# Leonardo_Rev3d.net
KiCad netlist of a schematic drawn in EAGLE
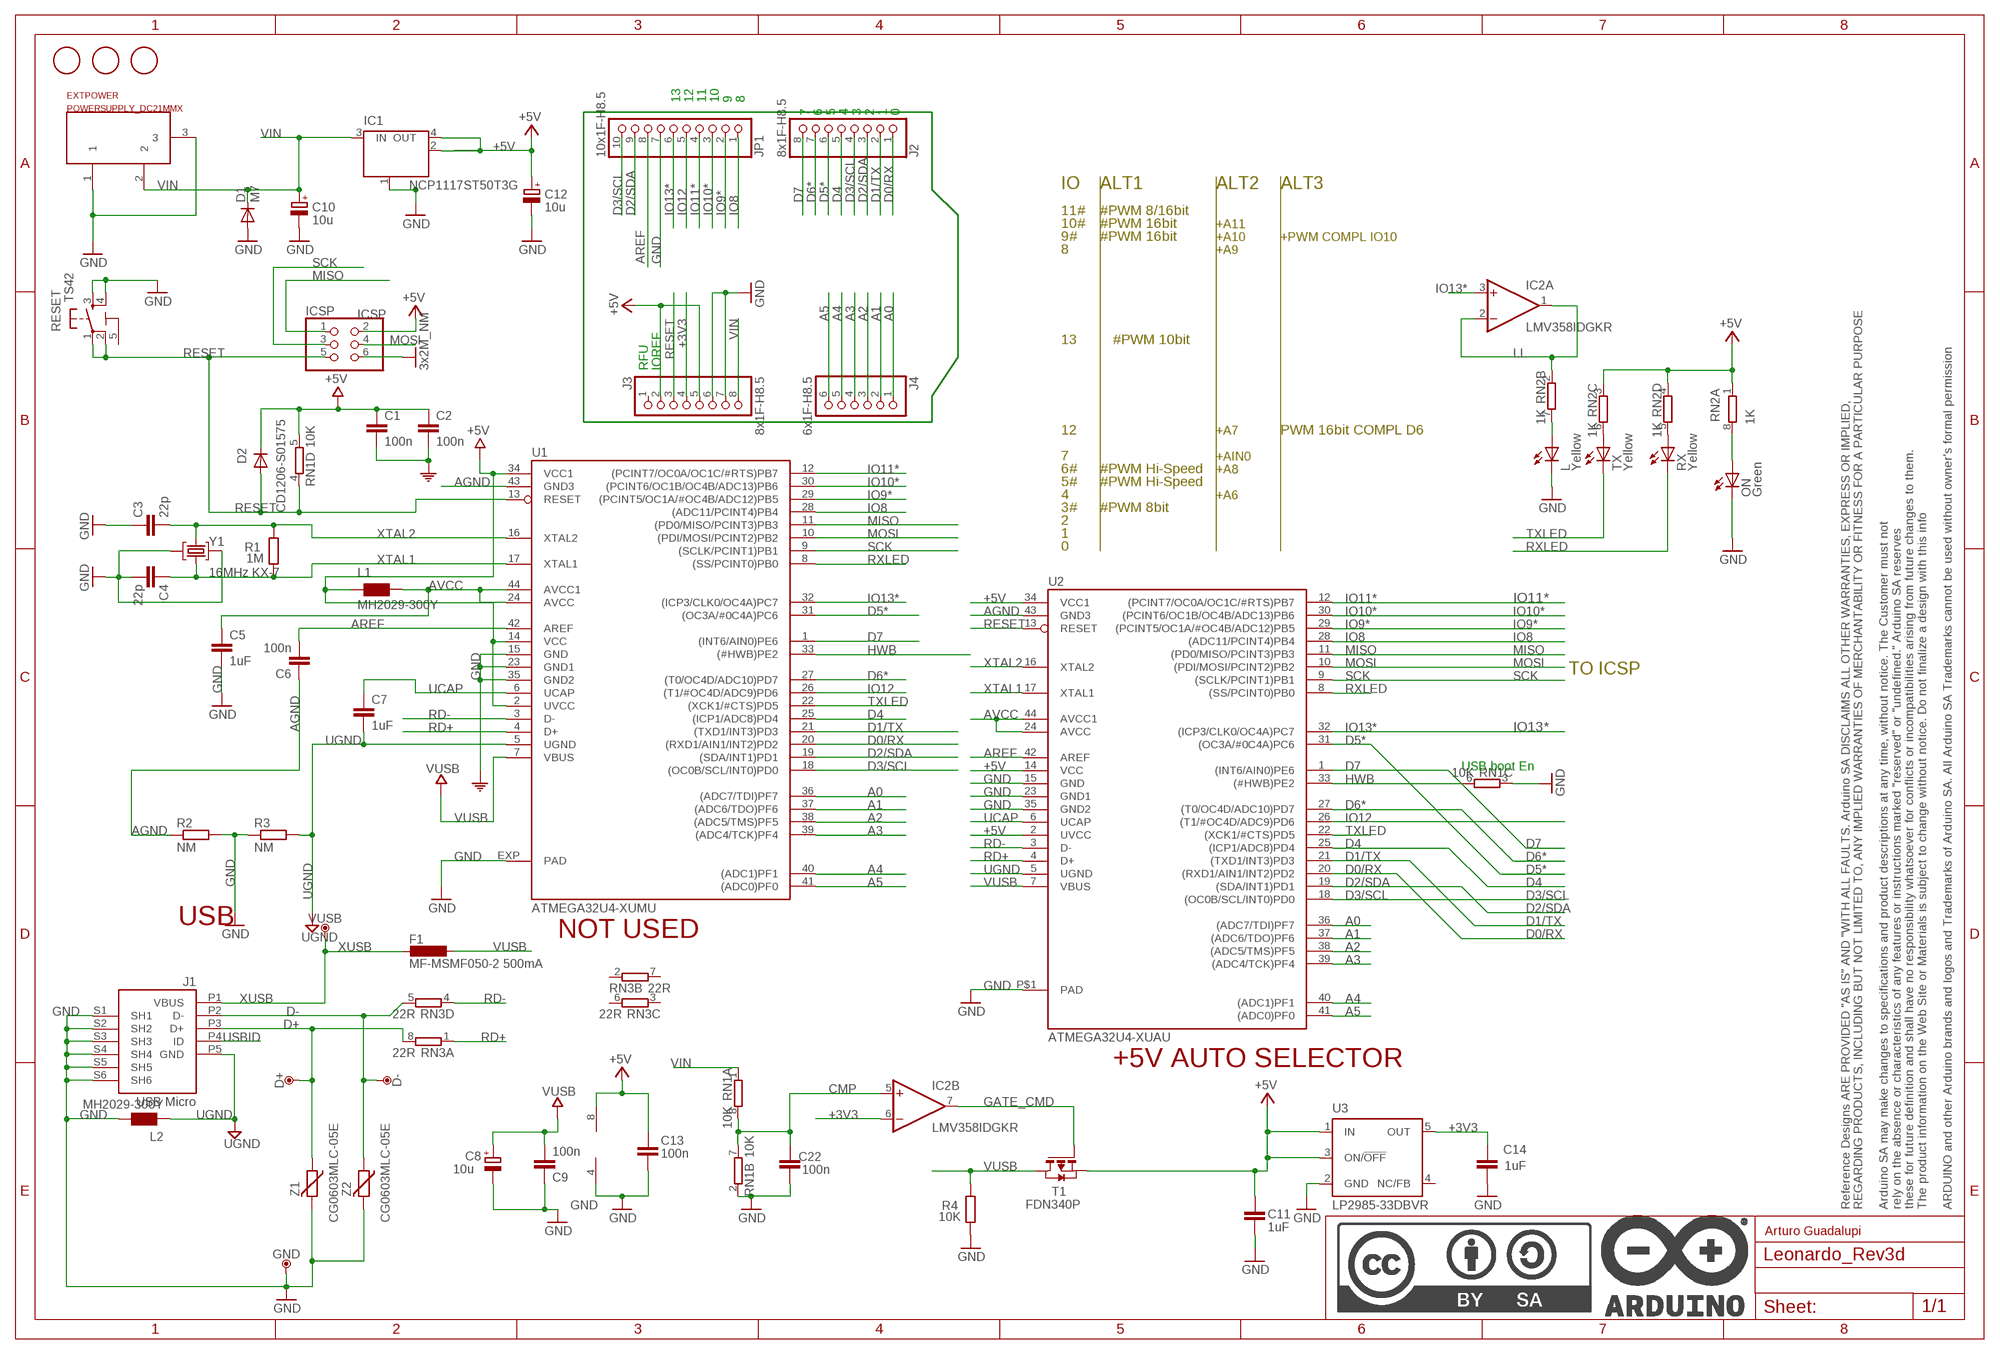
[diagram p0: schematic, sheet 1]

(export (version "E")
  (design (tool "Eeschema 10.0.6"))
  (components
    (comp (ref "C1")
      (value "100n")
      (footprint "eagle-import:C0603-ROUND")
      (libsource (lib "eagle-import") (part "C-EUC0603"))
    )
    (comp (ref "C2")
      (value "100n")
      (footprint "eagle-import:C0603-ROUND")
      (libsource (lib "eagle-import") (part "C-EUC0603"))
    )
    (comp (ref "C3")
      (value "22p")
      (footprint "eagle-import:C0603-ROUND")
      (libsource (lib "eagle-import") (part "C-EUC0603"))
    )
    (comp (ref "C4")
      (value "22p")
      (footprint "eagle-import:C0603-ROUND")
      (libsource (lib "eagle-import") (part "C-EUC0603"))
    )
    (comp (ref "C5")
      (value "1uF")
      (footprint "eagle-import:C0603-ROUND")
      (libsource (lib "eagle-import") (part "C-EUC0603"))
    )
    (comp (ref "C6")
      (value "100n")
      (footprint "eagle-import:C0603-ROUND")
      (libsource (lib "eagle-import") (part "C-EUC0603"))
    )
    (comp (ref "C7")
      (value "1uF")
      (footprint "eagle-import:C0603-ROUND")
      (libsource (lib "eagle-import") (part "C-EUC0603"))
    )
    (comp (ref "C8")
      (value "10u")
      (footprint "eagle-import:SMC_B")
      (libsource (lib "eagle-import") (part "CPOL-EUSMCB"))
    )
    (comp (ref "C9")
      (value "100n")
      (footprint "eagle-import:C0603-ROUND")
      (libsource (lib "eagle-import") (part "C-EUC0603"))
    )
    (comp (ref "C10")
      (value "10u")
      (footprint "eagle-import:SMC_B")
      (libsource (lib "eagle-import") (part "CPOL-EUSMCB"))
    )
    (comp (ref "C11")
      (value "1uF")
      (footprint "eagle-import:C0603-ROUND")
      (libsource (lib "eagle-import") (part "C-EUC0603"))
    )
    (comp (ref "C12")
      (value "10u")
      (footprint "eagle-import:SMC_B")
      (libsource (lib "eagle-import") (part "CPOL-EUSMCB"))
    )
    (comp (ref "C13")
      (value "100n")
      (footprint "eagle-import:C0603-ROUND")
      (libsource (lib "eagle-import") (part "C-EUC0603"))
    )
    (comp (ref "C14")
      (value "1uF")
      (footprint "eagle-import:C0603-ROUND")
      (libsource (lib "eagle-import") (part "C-EUC0603"))
    )
    (comp (ref "C22")
      (value "100n")
      (footprint "eagle-import:C0603-ROUND")
      (libsource (lib "eagle-import") (part "C-EUC0603"))
    )
    (comp (ref "D+")
      (value "DNP")
      (footprint "eagle-import:TP-1.00MM")
      (libsource (lib "eagle-import") (part "TPTP-1.00MM"))
    )
    (comp (ref "D-")
      (value "DNP")
      (footprint "eagle-import:TP-1.00MM")
      (libsource (lib "eagle-import") (part "TPTP-1.00MM"))
    )
    (comp (ref "D1")
      (value "M7")
      (footprint "eagle-import:SMB")
      (libsource (lib "eagle-import") (part "DIODE-SMB"))
    )
    (comp (ref "D2")
      (value "CD1206-S01575")
      (footprint "eagle-import:MINIMELF")
      (libsource (lib "eagle-import") (part "DIODE-MINIMELF"))
    )
    (comp (ref "EXTPOWER")
      (value "POWERSUPPLY_DC21MMX")
      (footprint "eagle-import:POWERSUPPLY_DC-21MM")
      (libsource (lib "eagle-import") (part "POWERSUPPLY_DC21MMX"))
    )
    (comp (ref "F1")
      (value "MF-MSMF050-2 500mA")
      (footprint "eagle-import:L1812")
      (libsource (lib "eagle-import") (part "L-EUL1812"))
    )
    (comp (ref "FID1")
      (value "DNP")
      (footprint "eagle-import:FD-1-1.5")
      (libsource (lib "eagle-import") (part "FIDUCIAL-1.5MM"))
    )
    (comp (ref "FID2")
      (value "DNP")
      (footprint "eagle-import:FD-1-1.5")
      (libsource (lib "eagle-import") (part "FIDUCIAL-1.5MM"))
    )
    (comp (ref "FID3")
      (value "DNP")
      (footprint "eagle-import:FD-1-1.5")
      (libsource (lib "eagle-import") (part "FIDUCIAL-1.5MM"))
    )
    (comp (ref "FRAME1")
      (value "DNP")
      (footprint "eagle-import:FRAME")
      (libsource (lib "eagle-import") (part "A3-FRAME"))
    )
    (comp (ref "GND")
      (value "DNP")
      (footprint "eagle-import:TP-1.00MM")
      (libsource (lib "eagle-import") (part "TPTP-1.00MM"))
    )
    (comp (ref "IC1")
      (value "NCP1117ST50T3G")
      (footprint "eagle-import:SOT223")
      (libsource (lib "eagle-import") (part "MC33269ST-3.3T3"))
    )
    (comp (ref "IC2")
      (value "LMV358IDGKR")
      (footprint "eagle-import:MSOP08")
      (libsource (lib "eagle-import") (part "LMV358?MMX"))
    )
    (comp (ref "ICSP")
      (value "ICSP")
      (footprint "eagle-import:2X03")
      (libsource (lib "eagle-import") (part "PINHD-2X3"))
    )
    (comp (ref "J1")
      (value "USB Micro")
      (footprint "eagle-import:CON2_USB_MICRO_B_AT")
      (fields (field (name "MANUFACTURER") "FCI"))
      (libsource (lib "eagle-import") (part "USB-MICRO-LEGACY"))
    )
    (comp (ref "J2")
      (value "8x1F-H8.5")
      (footprint "eagle-import:1X08")
      (libsource (lib "eagle-import") (part "PINHD-1X8"))
    )
    (comp (ref "J3")
      (value "8x1F-H8.5")
      (footprint "eagle-import:1X08")
      (libsource (lib "eagle-import") (part "PINHD-1X8"))
    )
    (comp (ref "J4")
      (value "6x1F-H8.5")
      (footprint "eagle-import:1X06")
      (libsource (lib "eagle-import") (part "PINHD-1X6"))
    )
    (comp (ref "JP1")
      (value "10x1F-H8.5")
      (footprint "eagle-import:1X10")
      (libsource (lib "eagle-import") (part "PINHD-1X10"))
    )
    (comp (ref "L")
      (value "Yellow")
      (footprint "eagle-import:CHIPLED_0805")
      (libsource (lib "eagle-import") (part "LEDCHIPLED_0805"))
    )
    (comp (ref "L1")
      (value "MH2029-300Y")
      (footprint "eagle-import:0805")
      (libsource (lib "eagle-import") (part "WE-CBF_0805"))
    )
    (comp (ref "L2")
      (value "MH2029-300Y")
      (footprint "eagle-import:0805")
      (libsource (lib "eagle-import") (part "WE-CBF_0805"))
    )
    (comp (ref "ON")
      (value "Green")
      (footprint "eagle-import:CHIPLED_0805")
      (libsource (lib "eagle-import") (part "LEDCHIPLED_0805"))
    )
    (comp (ref "R1")
      (value "1M")
      (footprint "eagle-import:R0603-ROUND")
      (libsource (lib "eagle-import") (part "R-EU_R0603"))
    )
    (comp (ref "R2")
      (value "NM")
      (footprint "eagle-import:R0402")
      (libsource (lib "eagle-import") (part "R-EU_R0402"))
    )
    (comp (ref "R3")
      (value "NM")
      (footprint "eagle-import:R0402")
      (libsource (lib "eagle-import") (part "R-EU_R0402"))
    )
    (comp (ref "R4")
      (value "10K")
      (footprint "eagle-import:R0603-ROUND")
      (libsource (lib "eagle-import") (part "R-EU_R0603"))
    )
    (comp (ref "RESET")
      (value "TS42")
      (footprint "eagle-import:TS42")
      (libsource (lib "eagle-import") (part "TS42"))
    )
    (comp (ref "RN1")
      (value "10K")
      (footprint "eagle-import:CAY16")
      (libsource (lib "eagle-import") (part "4R-NCAY16"))
    )
    (comp (ref "RN2")
      (value "1K")
      (footprint "eagle-import:CAY16")
      (libsource (lib "eagle-import") (part "4R-NCAY16"))
    )
    (comp (ref "RN3")
      (value "22R")
      (footprint "eagle-import:CAY16")
      (libsource (lib "eagle-import") (part "4R-NCAY16"))
    )
    (comp (ref "RX")
      (value "Yellow")
      (footprint "eagle-import:CHIPLED_0805")
      (libsource (lib "eagle-import") (part "LEDCHIPLED_0805"))
    )
    (comp (ref "T1")
      (value "FDN340P")
      (footprint "eagle-import:SOT-23")
      (libsource (lib "eagle-import") (part "PMOSSOT23"))
    )
    (comp (ref "TX")
      (value "Yellow")
      (footprint "eagle-import:CHIPLED_0805")
      (libsource (lib "eagle-import") (part "LEDCHIPLED_0805"))
    )
    (comp (ref "U1")
      (value "ATMEGA32U4-XUMU")
      (footprint "eagle-import:QFN44ML7X7")
      (libsource (lib "eagle-import") (part "ATMEGA32U4-XUMU"))
    )
    (comp (ref "U2")
      (value "ATMEGA32U4-XUAU")
      (footprint "eagle-import:TQFP44-PAD")
      (libsource (lib "eagle-import") (part "ATMEGA32U4-XUAU"))
    )
    (comp (ref "U3")
      (value "LP2985-33DBVR")
      (footprint "eagle-import:SOT23-DBV")
      (libsource (lib "eagle-import") (part "LP2985-XXDBVR33"))
    )
    (comp (ref "VUSB")
      (value "DNP")
      (footprint "eagle-import:TP-1.00MM")
      (libsource (lib "eagle-import") (part "TPTP-1.00MM"))
    )
    (comp (ref "Y1")
      (value "16MHz KX-7")
      (footprint "eagle-import:CRYSTAL-3.2-2.5")
      (libsource (lib "eagle-import") (part "CRYSTAL-3.2-2.5"))
    )
    (comp (ref "Z1")
      (value "CG0603MLC-05E")
      (footprint "eagle-import:CT_CN0603")
      (libsource (lib "eagle-import") (part "VARISTORCN0603"))
    )
    (comp (ref "Z2")
      (value "CG0603MLC-05E")
      (footprint "eagle-import:CT_CN0603")
      (libsource (lib "eagle-import") (part "VARISTORCN0603"))
    )
  )
  (nets
    (net (code "1") (name "+5V") (class "Default")
      (node (ref "C1") (pin "1") (pinfunction "1_1") (pintype "passive"))
      (node (ref "C11") (pin "2") (pinfunction "2_2") (pintype "passive"))
      (node (ref "C12") (pin "+") (pinfunction "+_+") (pintype "passive"))
      (node (ref "C13") (pin "1") (pinfunction "1_1") (pintype "passive"))
      (node (ref "C2") (pin "1") (pinfunction "1_1") (pintype "passive"))
      (node (ref "D2") (pin "C") (pinfunction "C_C") (pintype "passive"))
      (node (ref "IC1") (pin "2") (pinfunction "OUT_2") (pintype "passive"))
      (node (ref "IC1") (pin "4") (pinfunction "OUT_4") (pintype "passive"))
      (node (ref "IC2") (pin "8") (pinfunction "V+_8") (pintype "power_in"))
      (node (ref "ICSP") (pin "2") (pinfunction "2_2") (pintype "passive"))
      (node (ref "J3") (pin "2") (pinfunction "2_2") (pintype "passive"))
      (node (ref "J3") (pin "5") (pinfunction "5_5") (pintype "passive"))
      (node (ref "L1") (pin "1") (pinfunction "1_1") (pintype "passive"))
      (node (ref "RN1") (pin "5") (pinfunction "2_5") (pintype "passive"))
      (node (ref "RN2") (pin "1") (pinfunction "1_1") (pintype "passive"))
      (node (ref "RN2") (pin "3") (pinfunction "1_3") (pintype "passive"))
      (node (ref "RN2") (pin "4") (pinfunction "1_4") (pintype "passive"))
      (node (ref "T1") (pin "2") (pinfunction "S_2") (pintype "passive"))
      (node (ref "U1") (pin "14") (pinfunction "VCC_14") (pintype "power_in"))
      (node (ref "U1") (pin "2") (pinfunction "UVCC_2") (pintype "power_in"))
      (node (ref "U1") (pin "34") (pinfunction "VCC1_34") (pintype "power_in"))
      (node (ref "U2") (pin "14") (pinfunction "VCC_14") (pintype "power_in"))
      (node (ref "U2") (pin "2") (pinfunction "UVCC_2") (pintype "power_in"))
      (node (ref "U2") (pin "34") (pinfunction "VCC1_34") (pintype "power_in"))
      (node (ref "U3") (pin "1") (pinfunction "IN_1") (pintype "input"))
      (node (ref "U3") (pin "3") (pinfunction "ON/~{OFF}_3") (pintype "input"))
    )
    (net (code "2") (name "/+3V3") (class "Default")
      (node (ref "C14") (pin "2") (pinfunction "2_2") (pintype "passive"))
      (node (ref "IC2") (pin "6") (pinfunction "-IN_6") (pintype "input"))
      (node (ref "J3") (pin "4") (pinfunction "4_4") (pintype "passive"))
      (node (ref "U3") (pin "5") (pinfunction "OUT_5") (pintype "passive"))
    )
    (net (code "3") (name "/5-GND") (class "Default")
      (node (ref "RESET") (pin "5") (pinfunction "5-GND_5") (pintype "power_in"))
    )
    (net (code "4") (name "/A0") (class "Default")
      (node (ref "J4") (pin "1") (pinfunction "1_1") (pintype "passive"))
      (node (ref "U1") (pin "36") (pinfunction "(ADC7/TDI)PF7_36") (pintype "bidirectional"))
      (node (ref "U2") (pin "36") (pinfunction "(ADC7/TDI)PF7_36") (pintype "bidirectional"))
    )
    (net (code "5") (name "/A1") (class "Default")
      (node (ref "J4") (pin "2") (pinfunction "2_2") (pintype "passive"))
      (node (ref "U1") (pin "37") (pinfunction "(ADC6/TDO)PF6_37") (pintype "bidirectional"))
      (node (ref "U2") (pin "37") (pinfunction "(ADC6/TDO)PF6_37") (pintype "bidirectional"))
    )
    (net (code "6") (name "/A2") (class "Default")
      (node (ref "J4") (pin "3") (pinfunction "3_3") (pintype "passive"))
      (node (ref "U1") (pin "38") (pinfunction "(ADC5/TMS)PF5_38") (pintype "bidirectional"))
      (node (ref "U2") (pin "38") (pinfunction "(ADC5/TMS)PF5_38") (pintype "bidirectional"))
    )
    (net (code "7") (name "/A3") (class "Default")
      (node (ref "J4") (pin "4") (pinfunction "4_4") (pintype "passive"))
      (node (ref "U1") (pin "39") (pinfunction "(ADC4/TCK)PF4_39") (pintype "bidirectional"))
      (node (ref "U2") (pin "39") (pinfunction "(ADC4/TCK)PF4_39") (pintype "bidirectional"))
    )
    (net (code "8") (name "/A4") (class "Default")
      (node (ref "J4") (pin "5") (pinfunction "5_5") (pintype "passive"))
      (node (ref "U1") (pin "40") (pinfunction "(ADC1)PF1_40") (pintype "bidirectional"))
      (node (ref "U2") (pin "40") (pinfunction "(ADC1)PF1_40") (pintype "bidirectional"))
    )
    (net (code "9") (name "/A5") (class "Default")
      (node (ref "J4") (pin "6") (pinfunction "6_6") (pintype "passive"))
      (node (ref "U1") (pin "41") (pinfunction "(ADC0)PF0_41") (pintype "bidirectional"))
      (node (ref "U2") (pin "41") (pinfunction "(ADC0)PF0_41") (pintype "bidirectional"))
    )
    (net (code "10") (name "/AGND") (class "Default")
      (node (ref "C6") (pin "1") (pinfunction "1_1") (pintype "passive"))
      (node (ref "R2") (pin "1") (pinfunction "1_1") (pintype "passive"))
      (node (ref "U1") (pin "43") (pinfunction "GND3_43") (pintype "power_in"))
      (node (ref "U2") (pin "43") (pinfunction "GND3_43") (pintype "power_in"))
    )
    (net (code "11") (name "/AREF") (class "Default")
      (node (ref "C6") (pin "2") (pinfunction "2_2") (pintype "passive"))
      (node (ref "JP1") (pin "8") (pinfunction "8_8") (pintype "passive"))
      (node (ref "U1") (pin "42") (pinfunction "AREF_42") (pintype "power_in"))
      (node (ref "U2") (pin "42") (pinfunction "AREF_42") (pintype "power_in"))
    )
    (net (code "12") (name "/AVCC") (class "Default")
      (node (ref "C5") (pin "1") (pinfunction "1_1") (pintype "passive"))
      (node (ref "L1") (pin "2") (pinfunction "2_2") (pintype "passive"))
      (node (ref "U1") (pin "24") (pinfunction "AVCC_24") (pintype "power_in"))
      (node (ref "U1") (pin "44") (pinfunction "AVCC1_44") (pintype "power_in"))
      (node (ref "U2") (pin "24") (pinfunction "AVCC_24") (pintype "power_in"))
      (node (ref "U2") (pin "44") (pinfunction "AVCC1_44") (pintype "power_in"))
    )
    (net (code "13") (name "/CMP") (class "Default")
      (node (ref "C22") (pin "2") (pinfunction "2_2") (pintype "passive"))
      (node (ref "IC2") (pin "5") (pinfunction "+IN_5") (pintype "input"))
      (node (ref "RN1") (pin "7") (pinfunction "2_7") (pintype "passive"))
      (node (ref "RN1") (pin "8") (pinfunction "2_8") (pintype "passive"))
    )
    (net (code "14") (name "/D+") (class "Default")
      (node (ref "D+") (pin "X") (pinfunction "P$1_X") (pintype "passive"))
      (node (ref "J1") (pin "P3") (pinfunction "D+_P3") (pintype "bidirectional"))
      (node (ref "RN3") (pin "8") (pinfunction "2_8") (pintype "passive"))
      (node (ref "Z1") (pin "1") (pinfunction "1_1") (pintype "passive"))
    )
    (net (code "15") (name "/D-") (class "Default")
      (node (ref "D-") (pin "X") (pinfunction "P$1_X") (pintype "passive"))
      (node (ref "J1") (pin "P2") (pinfunction "D-_P2") (pintype "bidirectional"))
      (node (ref "RN3") (pin "5") (pinfunction "2_5") (pintype "passive"))
      (node (ref "Z2") (pin "1") (pinfunction "1_1") (pintype "passive"))
    )
    (net (code "16") (name "/D0{slash}RX") (class "Default")
      (node (ref "J2") (pin "1") (pinfunction "1_1") (pintype "passive"))
      (node (ref "U1") (pin "20") (pinfunction "(RXD1/AIN1/INT2)PD2_20") (pintype "bidirectional"))
      (node (ref "U2") (pin "20") (pinfunction "(RXD1/AIN1/INT2)PD2_20") (pintype "bidirectional"))
    )
    (net (code "17") (name "/D1{slash}TX") (class "Default")
      (node (ref "J2") (pin "2") (pinfunction "2_2") (pintype "passive"))
      (node (ref "U1") (pin "21") (pinfunction "(TXD1/INT3)PD3_21") (pintype "bidirectional"))
      (node (ref "U2") (pin "21") (pinfunction "(TXD1/INT3)PD3_21") (pintype "bidirectional"))
    )
    (net (code "18") (name "/D2{slash}SDA") (class "Default")
      (node (ref "J2") (pin "3") (pinfunction "3_3") (pintype "passive"))
      (node (ref "JP1") (pin "9") (pinfunction "9_9") (pintype "passive"))
      (node (ref "U1") (pin "19") (pinfunction "(SDA/INT1)PD1_19") (pintype "bidirectional"))
      (node (ref "U2") (pin "19") (pinfunction "(SDA/INT1)PD1_19") (pintype "bidirectional"))
    )
    (net (code "19") (name "/D3{slash}SCL") (class "Default")
      (node (ref "J2") (pin "4") (pinfunction "4_4") (pintype "passive"))
      (node (ref "JP1") (pin "10") (pinfunction "10_10") (pintype "passive"))
      (node (ref "U1") (pin "18") (pinfunction "(OC0B/SCL/INT0)PD0_18") (pintype "bidirectional"))
      (node (ref "U2") (pin "18") (pinfunction "(OC0B/SCL/INT0)PD0_18") (pintype "bidirectional"))
    )
    (net (code "20") (name "/D4") (class "Default")
      (node (ref "J2") (pin "5") (pinfunction "5_5") (pintype "passive"))
      (node (ref "U1") (pin "25") (pinfunction "(ICP1/ADC8)PD4_25") (pintype "bidirectional"))
      (node (ref "U2") (pin "25") (pinfunction "(ICP1/ADC8)PD4_25") (pintype "bidirectional"))
    )
    (net (code "21") (name "/D5*") (class "Default")
      (node (ref "J2") (pin "6") (pinfunction "6_6") (pintype "passive"))
      (node (ref "U1") (pin "31") (pinfunction "(OC3A/#0C4A)PC6_31") (pintype "bidirectional"))
      (node (ref "U2") (pin "31") (pinfunction "(OC3A/#0C4A)PC6_31") (pintype "bidirectional"))
    )
    (net (code "22") (name "/D6*") (class "Default")
      (node (ref "J2") (pin "7") (pinfunction "7_7") (pintype "passive"))
      (node (ref "U1") (pin "27") (pinfunction "(T0/OC4D/ADC10)PD7_27") (pintype "bidirectional"))
      (node (ref "U2") (pin "27") (pinfunction "(T0/OC4D/ADC10)PD7_27") (pintype "bidirectional"))
    )
    (net (code "23") (name "/D7") (class "Default")
      (node (ref "J2") (pin "8") (pinfunction "8_8") (pintype "passive"))
      (node (ref "U1") (pin "1") (pinfunction "(INT6/AIN0)PE6_1") (pintype "bidirectional"))
      (node (ref "U2") (pin "1") (pinfunction "(INT6/AIN0)PE6_1") (pintype "bidirectional"))
    )
    (net (code "24") (name "/GATE_CMD") (class "Default")
      (node (ref "IC2") (pin "7") (pinfunction "OUT_7") (pintype "output"))
      (node (ref "T1") (pin "3") (pinfunction "G_3") (pintype "passive"))
    )
    (net (code "25") (name "/HWB") (class "Default")
      (node (ref "RN1") (pin "6") (pinfunction "2_6") (pintype "passive"))
      (node (ref "U1") (pin "33") (pinfunction "(#HWB)PE2_33") (pintype "bidirectional"))
      (node (ref "U2") (pin "33") (pinfunction "(#HWB)PE2_33") (pintype "bidirectional"))
    )
    (net (code "26") (name "/IO8") (class "Default")
      (node (ref "JP1") (pin "1") (pinfunction "1_1") (pintype "passive"))
      (node (ref "U1") (pin "28") (pinfunction "(ADC11/PCINT4)PB4_28") (pintype "bidirectional"))
      (node (ref "U2") (pin "28") (pinfunction "(ADC11/PCINT4)PB4_28") (pintype "bidirectional"))
    )
    (net (code "27") (name "/IO9*") (class "Default")
      (node (ref "JP1") (pin "2") (pinfunction "2_2") (pintype "passive"))
      (node (ref "U1") (pin "29") (pinfunction "(PCINT5/OC1A/#OC4B/ADC12)PB5_29") (pintype "bidirectional"))
      (node (ref "U2") (pin "29") (pinfunction "(PCINT5/OC1A/#OC4B/ADC12)PB5_29") (pintype "bidirectional"))
    )
    (net (code "28") (name "/IO10*") (class "Default")
      (node (ref "JP1") (pin "3") (pinfunction "3_3") (pintype "passive"))
      (node (ref "U1") (pin "30") (pinfunction "(PCINT6/OC1B/OC4B/ADC13)PB6_30") (pintype "bidirectional"))
      (node (ref "U2") (pin "30") (pinfunction "(PCINT6/OC1B/OC4B/ADC13)PB6_30") (pintype "bidirectional"))
    )
    (net (code "29") (name "/IO11*") (class "Default")
      (node (ref "JP1") (pin "4") (pinfunction "4_4") (pintype "passive"))
      (node (ref "U1") (pin "12") (pinfunction "(PCINT7/OC0A/OC1C/#RTS)PB7_12") (pintype "bidirectional"))
      (node (ref "U2") (pin "12") (pinfunction "(PCINT7/OC0A/OC1C/#RTS)PB7_12") (pintype "bidirectional"))
    )
    (net (code "30") (name "/IO12") (class "Default")
      (node (ref "JP1") (pin "5") (pinfunction "5_5") (pintype "passive"))
      (node (ref "U1") (pin "26") (pinfunction "(T1/#OC4D/ADC9)PD6_26") (pintype "bidirectional"))
      (node (ref "U2") (pin "26") (pinfunction "(T1/#OC4D/ADC9)PD6_26") (pintype "bidirectional"))
    )
    (net (code "31") (name "/IO13*") (class "Default")
      (node (ref "IC2") (pin "3") (pinfunction "+IN_3") (pintype "input"))
      (node (ref "JP1") (pin "6") (pinfunction "6_6") (pintype "passive"))
      (node (ref "U1") (pin "32") (pinfunction "(ICP3/CLK0/OC4A)PC7_32") (pintype "bidirectional"))
      (node (ref "U2") (pin "32") (pinfunction "(ICP3/CLK0/OC4A)PC7_32") (pintype "bidirectional"))
    )
    (net (code "32") (name "/LL") (class "Default")
      (node (ref "IC2") (pin "1") (pinfunction "OUT_1") (pintype "output"))
      (node (ref "IC2") (pin "2") (pinfunction "-IN_2") (pintype "input"))
      (node (ref "RN2") (pin "2") (pinfunction "1_2") (pintype "passive"))
    )
    (net (code "33") (name "/MISO") (class "Default")
      (node (ref "ICSP") (pin "1") (pinfunction "1_1") (pintype "passive"))
      (node (ref "U1") (pin "11") (pinfunction "(PD0/MISO/PCINT3)PB3_11") (pintype "bidirectional"))
      (node (ref "U2") (pin "11") (pinfunction "(PD0/MISO/PCINT3)PB3_11") (pintype "bidirectional"))
    )
    (net (code "34") (name "/MOSI") (class "Default")
      (node (ref "ICSP") (pin "4") (pinfunction "4_4") (pintype "passive"))
      (node (ref "U1") (pin "10") (pinfunction "(PDI/MOSI/PCINT2)PB2_10") (pintype "bidirectional"))
      (node (ref "U2") (pin "10") (pinfunction "(PDI/MOSI/PCINT2)PB2_10") (pintype "bidirectional"))
    )
    (net (code "35") (name "/RD+") (class "Default")
      (node (ref "RN3") (pin "1") (pinfunction "1_1") (pintype "passive"))
      (node (ref "U1") (pin "4") (pinfunction "D+_4") (pintype "bidirectional"))
      (node (ref "U2") (pin "4") (pinfunction "D+_4") (pintype "bidirectional"))
    )
    (net (code "36") (name "/RD-") (class "Default")
      (node (ref "RN3") (pin "4") (pinfunction "1_4") (pintype "passive"))
      (node (ref "U1") (pin "3") (pinfunction "D-_3") (pintype "bidirectional"))
      (node (ref "U2") (pin "3") (pinfunction "D-_3") (pintype "bidirectional"))
    )
    (net (code "37") (name "/RESET") (class "Default")
      (node (ref "D2") (pin "A") (pinfunction "A_A") (pintype "passive"))
      (node (ref "ICSP") (pin "5") (pinfunction "5_5") (pintype "passive"))
      (node (ref "J3") (pin "3") (pinfunction "3_3") (pintype "passive"))
      (node (ref "RESET") (pin "1") (pinfunction "1_1") (pintype "passive"))
      (node (ref "RESET") (pin "2") (pinfunction "2_2") (pintype "passive"))
      (node (ref "RN1") (pin "4") (pinfunction "1_4") (pintype "passive"))
      (node (ref "U1") (pin "13") (pinfunction "RESET_13") (pintype "input"))
      (node (ref "U2") (pin "13") (pinfunction "RESET_13") (pintype "input"))
    )
    (net (code "38") (name "/RXLED") (class "Default")
      (node (ref "RX") (pin "C") (pinfunction "C_C") (pintype "passive"))
      (node (ref "U1") (pin "8") (pinfunction "(SS/PCINT0)PB0_8") (pintype "bidirectional"))
      (node (ref "U2") (pin "8") (pinfunction "(SS/PCINT0)PB0_8") (pintype "bidirectional"))
    )
    (net (code "39") (name "/SCK") (class "Default")
      (node (ref "ICSP") (pin "3") (pinfunction "3_3") (pintype "passive"))
      (node (ref "U1") (pin "9") (pinfunction "(SCLK/PCINT1)PB1_9") (pintype "bidirectional"))
      (node (ref "U2") (pin "9") (pinfunction "(SCLK/PCINT1)PB1_9") (pintype "bidirectional"))
    )
    (net (code "40") (name "/TXLED") (class "Default")
      (node (ref "TX") (pin "C") (pinfunction "C_C") (pintype "passive"))
      (node (ref "U1") (pin "22") (pinfunction "(XCK1/#CTS)PD5_22") (pintype "bidirectional"))
      (node (ref "U2") (pin "22") (pinfunction "(XCK1/#CTS)PD5_22") (pintype "bidirectional"))
    )
    (net (code "41") (name "/UCAP") (class "Default")
      (node (ref "C7") (pin "1") (pinfunction "1_1") (pintype "passive"))
      (node (ref "U1") (pin "6") (pinfunction "UCAP_6") (pintype "passive"))
      (node (ref "U2") (pin "6") (pinfunction "UCAP_6") (pintype "passive"))
    )
    (net (code "42") (name "/USBID") (class "Default")
      (node (ref "J1") (pin "P4") (pinfunction "ID_P4") (pintype "bidirectional"))
    )
    (net (code "43") (name "/VIN") (class "Default")
      (node (ref "C10") (pin "+") (pinfunction "+_+") (pintype "passive"))
      (node (ref "D1") (pin "C") (pinfunction "C_C") (pintype "passive"))
      (node (ref "EXTPOWER") (pin "2") (pinfunction "2_2") (pintype "power_in"))
      (node (ref "IC1") (pin "3") (pinfunction "IN_3") (pintype "input"))
      (node (ref "J3") (pin "8") (pinfunction "8_8") (pintype "passive"))
      (node (ref "RN1") (pin "1") (pinfunction "1_1") (pintype "passive"))
    )
    (net (code "44") (name "/XTAL1") (class "Default")
      (node (ref "C4") (pin "1") (pinfunction "1_1") (pintype "passive"))
      (node (ref "R1") (pin "1") (pinfunction "1_1") (pintype "passive"))
      (node (ref "U1") (pin "17") (pinfunction "XTAL1_17") (pintype "bidirectional"))
      (node (ref "U2") (pin "17") (pinfunction "XTAL1_17") (pintype "bidirectional"))
      (node (ref "Y1") (pin "1") (pinfunction "C1_1") (pintype "passive"))
    )
    (net (code "45") (name "/XTAL2") (class "Default")
      (node (ref "C3") (pin "2") (pinfunction "2_2") (pintype "passive"))
      (node (ref "R1") (pin "2") (pinfunction "2_2") (pintype "passive"))
      (node (ref "U1") (pin "16") (pinfunction "XTAL2_16") (pintype "bidirectional"))
      (node (ref "U2") (pin "16") (pinfunction "XTAL2_16") (pintype "bidirectional"))
      (node (ref "Y1") (pin "3") (pinfunction "C2_3") (pintype "passive"))
    )
    (net (code "46") (name "/XUSB") (class "Default")
      (node (ref "F1") (pin "2") (pinfunction "2_2") (pintype "passive"))
      (node (ref "J1") (pin "P1") (pinfunction "VBUS_P1") (pintype "power_in"))
      (node (ref "VUSB") (pin "X") (pinfunction "P$1_X") (pintype "passive"))
    )
    (net (code "47") (name "3x2M_NM") (class "Default")
      (node (ref "C1") (pin "2") (pinfunction "2_2") (pintype "passive"))
      (node (ref "C10") (pin "-") (pinfunction "-_-") (pintype "passive"))
      (node (ref "C11") (pin "1") (pinfunction "1_1") (pintype "passive"))
      (node (ref "C12") (pin "-") (pinfunction "-_-") (pintype "passive"))
      (node (ref "C13") (pin "2") (pinfunction "2_2") (pintype "passive"))
      (node (ref "C14") (pin "1") (pinfunction "1_1") (pintype "passive"))
      (node (ref "C2") (pin "2") (pinfunction "2_2") (pintype "passive"))
      (node (ref "C22") (pin "1") (pinfunction "1_1") (pintype "passive"))
      (node (ref "C3") (pin "1") (pinfunction "1_1") (pintype "passive"))
      (node (ref "C4") (pin "2") (pinfunction "2_2") (pintype "passive"))
      (node (ref "C5") (pin "2") (pinfunction "2_2") (pintype "passive"))
      (node (ref "C8") (pin "-") (pinfunction "-_-") (pintype "passive"))
      (node (ref "C9") (pin "1") (pinfunction "1_1") (pintype "passive"))
      (node (ref "D1") (pin "A") (pinfunction "A_A") (pintype "passive"))
      (node (ref "EXTPOWER") (pin "1") (pinfunction "1_1") (pintype "power_in"))
      (node (ref "EXTPOWER") (pin "3") (pinfunction "3_3") (pintype "power_in"))
      (node (ref "GND") (pin "X") (pinfunction "P$1_X") (pintype "passive"))
      (node (ref "IC1") (pin "1") (pinfunction "GND/ADJ_1") (pintype "input"))
      (node (ref "IC2") (pin "4") (pinfunction "V-_4") (pintype "power_in"))
      (node (ref "ICSP") (pin "6") (pinfunction "6_6") (pintype "passive"))
      (node (ref "J1") (pin "S1") (pinfunction "SH1_S1") (pintype "passive"))
      (node (ref "J1") (pin "S2") (pinfunction "SH2_S2") (pintype "passive"))
      (node (ref "J1") (pin "S3") (pinfunction "SH3_S3") (pintype "passive"))
      (node (ref "J1") (pin "S4") (pinfunction "SH4_S4") (pintype "passive"))
      (node (ref "J1") (pin "S5") (pinfunction "SH5_S5") (pintype "passive"))
      (node (ref "J1") (pin "S6") (pinfunction "SH6_S6") (pintype "passive"))
      (node (ref "J3") (pin "6") (pinfunction "6_6") (pintype "passive"))
      (node (ref "J3") (pin "7") (pinfunction "7_7") (pintype "passive"))
      (node (ref "JP1") (pin "7") (pinfunction "7_7") (pintype "passive"))
      (node (ref "L") (pin "C") (pinfunction "C_C") (pintype "passive"))
      (node (ref "L2") (pin "2") (pinfunction "2_2") (pintype "passive"))
      (node (ref "ON") (pin "C") (pinfunction "C_C") (pintype "passive"))
      (node (ref "R2") (pin "2") (pinfunction "2_2") (pintype "passive"))
      (node (ref "R3") (pin "1") (pinfunction "1_1") (pintype "passive"))
      (node (ref "R4") (pin "1") (pinfunction "1_1") (pintype "passive"))
      (node (ref "RESET") (pin "3") (pinfunction "3_3") (pintype "passive"))
      (node (ref "RESET") (pin "4") (pinfunction "4_4") (pintype "passive"))
      (node (ref "RN1") (pin "2") (pinfunction "1_2") (pintype "passive"))
      (node (ref "RN1") (pin "3") (pinfunction "1_3") (pintype "passive"))
      (node (ref "U1") (pin "15") (pinfunction "GND_15") (pintype "power_in"))
      (node (ref "U1") (pin "23") (pinfunction "GND1_23") (pintype "power_in"))
      (node (ref "U1") (pin "35") (pinfunction "GND2_35") (pintype "power_in"))
      (node (ref "U1") (pin "EXP") (pinfunction "PAD_EXP") (pintype "power_in"))
      (node (ref "U2") (pin "15") (pinfunction "GND_15") (pintype "power_in"))
      (node (ref "U2") (pin "23") (pinfunction "GND1_23") (pintype "power_in"))
      (node (ref "U2") (pin "35") (pinfunction "GND2_35") (pintype "power_in"))
      (node (ref "U2") (pin "P$1") (pinfunction "PAD_P$1") (pintype "power_in"))
      (node (ref "U3") (pin "2") (pinfunction "GND_2") (pintype "power_in"))
      (node (ref "Y1") (pin "2") (pinfunction "GND_2") (pintype "passive"))
      (node (ref "Y1") (pin "4") (pinfunction "GND_4") (pintype "passive"))
      (node (ref "Z1") (pin "2") (pinfunction "2_2") (pintype "passive"))
      (node (ref "Z2") (pin "2") (pinfunction "2_2") (pintype "passive"))
    )
    (net (code "48") (name "Net-(RN2A-2)") (class "Default")
      (node (ref "ON") (pin "A") (pinfunction "A_A") (pintype "passive"))
      (node (ref "RN2") (pin "8") (pinfunction "2_8") (pintype "passive"))
    )
    (net (code "49") (name "Net-(RN2B-2)") (class "Default")
      (node (ref "L") (pin "A") (pinfunction "A_A") (pintype "passive"))
      (node (ref "RN2") (pin "7") (pinfunction "2_7") (pintype "passive"))
    )
    (net (code "50") (name "Net-(RN2C-2)") (class "Default")
      (node (ref "RN2") (pin "6") (pinfunction "2_6") (pintype "passive"))
      (node (ref "TX") (pin "A") (pinfunction "A_A") (pintype "passive"))
    )
    (net (code "51") (name "Net-(RN2D-2)") (class "Default")
      (node (ref "RN2") (pin "5") (pinfunction "2_5") (pintype "passive"))
      (node (ref "RX") (pin "A") (pinfunction "A_A") (pintype "passive"))
    )
    (net (code "52") (name "UGND") (class "Default")
      (node (ref "C7") (pin "2") (pinfunction "2_2") (pintype "passive"))
      (node (ref "J1") (pin "P5") (pinfunction "GND_P5") (pintype "passive"))
      (node (ref "L2") (pin "1") (pinfunction "1_1") (pintype "passive"))
      (node (ref "R3") (pin "2") (pinfunction "2_2") (pintype "passive"))
      (node (ref "U1") (pin "5") (pinfunction "UGND_5") (pintype "power_in"))
      (node (ref "U2") (pin "5") (pinfunction "UGND_5") (pintype "power_in"))
    )
    (net (code "53") (name "VUSB") (class "Default")
      (node (ref "C8") (pin "+") (pinfunction "+_+") (pintype "passive"))
      (node (ref "C9") (pin "2") (pinfunction "2_2") (pintype "passive"))
      (node (ref "F1") (pin "1") (pinfunction "1_1") (pintype "passive"))
      (node (ref "R4") (pin "2") (pinfunction "2_2") (pintype "passive"))
      (node (ref "T1") (pin "1") (pinfunction "D_1") (pintype "passive"))
      (node (ref "U1") (pin "7") (pinfunction "VBUS_7") (pintype "input"))
      (node (ref "U2") (pin "7") (pinfunction "VBUS_7") (pintype "input"))
    )
    (net (code "54") (name "unconnected-(J3-Pad1)") (class "Default")
      (node (ref "J3") (pin "1") (pinfunction "1_1") (pintype "passive"))
    )
    (net (code "55") (name "unconnected-(RN3B-1-Pad2)") (class "Default")
      (node (ref "RN3") (pin "2") (pinfunction "1_2") (pintype "passive"))
    )
    (net (code "56") (name "unconnected-(RN3B-2-Pad7)") (class "Default")
      (node (ref "RN3") (pin "7") (pinfunction "2_7") (pintype "passive"))
    )
    (net (code "57") (name "unconnected-(RN3C-1-Pad3)") (class "Default")
      (node (ref "RN3") (pin "3") (pinfunction "1_3") (pintype "passive"))
    )
    (net (code "58") (name "unconnected-(RN3C-2-Pad6)") (class "Default")
      (node (ref "RN3") (pin "6") (pinfunction "2_6") (pintype "passive"))
    )
    (net (code "59") (name "unconnected-(U3-NC{slash}FB-Pad4)") (class "Default")
      (node (ref "U3") (pin "4") (pinfunction "NC/FB_4") (pintype "passive"))
    )
  )
)
